# Connections.net
KiCad netlist of a schematic drawn in Altium Designer
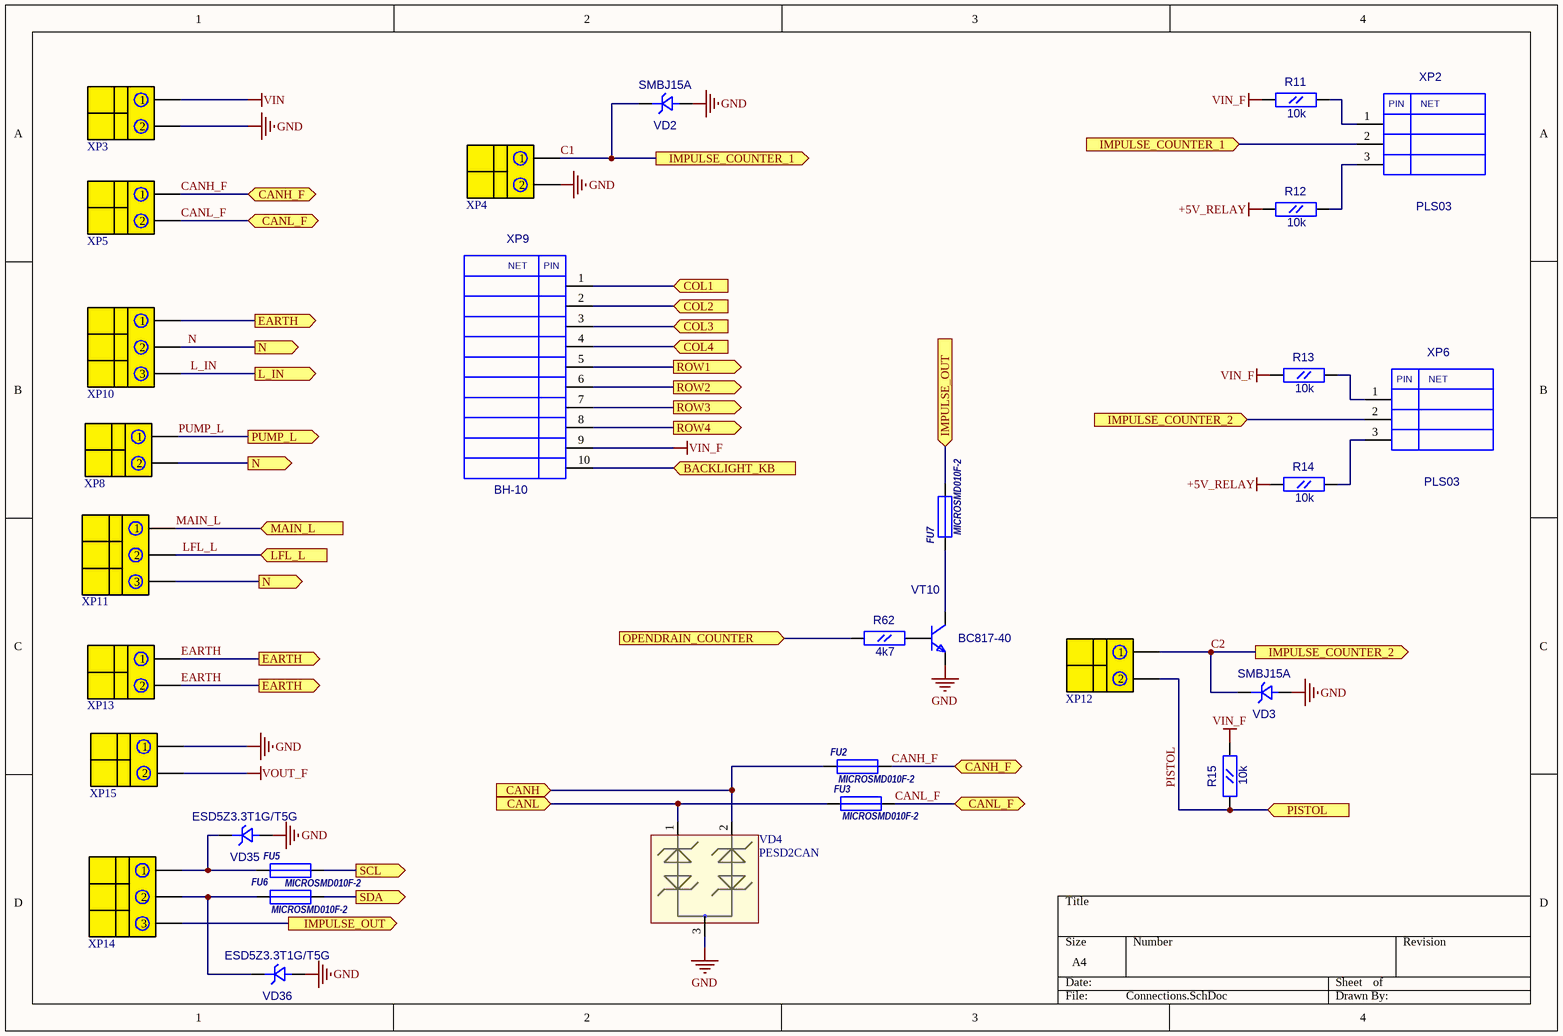
[diagram p0: Connections.SchDoc]

(export (version "E")
  (design (tool "Eeschema 10.0.6"))
  (components
    (comp (ref "FU2")
      (value "MICROSMD010F-2")
      (footprint "RC1210")
      (description "MICROSMD")
      (libsource (lib "gprs_modem_2") (part "MICROSMD"))
    )
    (comp (ref "FU3")
      (value "MICROSMD010F-2")
      (footprint "RC1210")
      (description "MICROSMD")
      (libsource (lib "gprs_modem_2") (part "MICROSMD"))
    )
    (comp (ref "FU5")
      (value "MICROSMD010F-2")
      (footprint "RC1210")
      (description "MICROSMD")
      (libsource (lib "gprs_modem_2") (part "MICROSMD"))
    )
    (comp (ref "FU6")
      (value "MICROSMD010F-2")
      (footprint "RC1210")
      (description "MICROSMD")
      (libsource (lib "gprs_modem_2") (part "MICROSMD"))
    )
    (comp (ref "FU7")
      (value "MICROSMD010F-2")
      (footprint "RC1210")
      (description "MICROSMD")
      (libsource (lib "gprs_modem_2") (part "MICROSMD"))
    )
    (comp (ref "R11")
      (value "10k")
      (footprint "RC0603")
      (description "RC0603")
      (libsource (lib "gprs_modem_2") (part "RC0603"))
    )
    (comp (ref "R12")
      (value "10k")
      (footprint "RC0603")
      (description "RC0603")
      (libsource (lib "gprs_modem_2") (part "RC0603"))
    )
    (comp (ref "R13")
      (value "10k")
      (footprint "RC0603")
      (description "RC0603")
      (libsource (lib "gprs_modem_2") (part "RC0603"))
    )
    (comp (ref "R14")
      (value "10k")
      (footprint "RC0603")
      (description "RC0603")
      (libsource (lib "gprs_modem_2") (part "RC0603"))
    )
    (comp (ref "R15")
      (value "10k")
      (footprint "RC0603")
      (description "RC0603")
      (libsource (lib "gprs_modem_2") (part "RC0603"))
    )
    (comp (ref "R62")
      (value "4k7")
      (footprint "RC0603")
      (description "RC0603")
      (libsource (lib "gprs_modem_2") (part "RC0603"))
    )
    (comp (ref "VD2")
      (value "SMBJ15A")
      (footprint "SMB")
      (description "SMBJ")
      (libsource (lib "gprs_modem_2") (part "SMBJ"))
    )
    (comp (ref "VD3")
      (value "SMBJ15A")
      (footprint "SMB")
      (description "SMBJ")
      (libsource (lib "gprs_modem_2") (part "SMBJ"))
    )
    (comp (ref "VD4")
      (value "PESD2CAN")
      (footprint "SOT-23(123)")
      (description "TVS for CAN")
      (libsource (lib "gprs_modem_2") (part "PESD2CAN"))
    )
    (comp (ref "VD35")
      (value "ESD5Z3.3T1G/T5G")
      (footprint "SOD-523")
      (description "Supressor")
      (libsource (lib "gprs_modem_2") (part "ESD5Z"))
    )
    (comp (ref "VD36")
      (value "ESD5Z3.3T1G/T5G")
      (footprint "SOD-523")
      (description "Supressor")
      (libsource (lib "gprs_modem_2") (part "ESD5Z"))
    )
    (comp (ref "VT10")
      (value "BC817-40")
      (footprint "SOT-23(123)")
      (description "NPN 500ma transistor")
      (libsource (lib "gprs_modem_2") (part "BC846BLT1"))
    )
    (comp (ref "XP2") (value "PLS03") (footprint "PLS-03") (libsource (lib "gprs_modem_2") (part "PLS03")))
    (comp (ref "XP3")
      (value "DG330-2PIN")
      (footprint "DG330-2PIN")
      (libsource (lib "gprs_modem_2") (part "DG330-2PIN"))
    )
    (comp (ref "XP4")
      (value "DG330-2PIN")
      (footprint "DG330-2PIN")
      (libsource (lib "gprs_modem_2") (part "DG330-2PIN"))
    )
    (comp (ref "XP5")
      (value "DG330-2PIN")
      (footprint "DG330-2PIN")
      (libsource (lib "gprs_modem_2") (part "DG330-2PIN"))
    )
    (comp (ref "XP6") (value "PLS03") (footprint "PLS-03") (libsource (lib "gprs_modem_2") (part "PLS03")))
    (comp (ref "XP8")
      (value "DG330-2PIN")
      (footprint "DG330-2PIN")
      (libsource (lib "gprs_modem_2") (part "DG330-2PIN"))
    )
    (comp (ref "XP9") (value "BH-10") (footprint "BH-10") (libsource (lib "gprs_modem_2") (part "BH-10")))
    (comp (ref "XP10")
      (value "DG330-3PIN")
      (footprint "DG330-3PIN")
      (libsource (lib "gprs_modem_2") (part "DG330-3PIN"))
    )
    (comp (ref "XP11")
      (value "DG330-3PIN")
      (footprint "DG330-3PIN")
      (libsource (lib "gprs_modem_2") (part "DG330-3PIN"))
    )
    (comp (ref "XP12")
      (value "DG330-2PIN")
      (footprint "DG330-2PIN")
      (libsource (lib "gprs_modem_2") (part "DG330-2PIN"))
    )
    (comp (ref "XP13")
      (value "DG330-2PIN")
      (footprint "DG330-2PIN")
      (libsource (lib "gprs_modem_2") (part "DG330-2PIN"))
    )
    (comp (ref "XP14")
      (value "DG330-3PIN")
      (footprint "DG330-3PIN")
      (libsource (lib "gprs_modem_2") (part "DG330-3PIN"))
    )
    (comp (ref "XP15")
      (value "DG330-2PIN")
      (footprint "DG330-2PIN")
      (libsource (lib "gprs_modem_2") (part "DG330-2PIN"))
    )
  )
  (nets
    (net (code "1") (name "+5V_RELAY") (class "Default")
      (node (ref "R12") (pin "1") (pinfunction "A_1") (pintype "passive"))
      (node (ref "R14") (pin "1") (pinfunction "A_1") (pintype "passive"))
    )
    (net (code "2") (name "/BACKLIGHT_KB") (class "Default")
      (node (ref "XP9") (pin "10") (pinfunction "10_10") (pintype "passive"))
    )
    (net (code "3") (name "/C1") (class "Default")
      (node (ref "VD2") (pin "2") (pinfunction "K_2") (pintype "passive"))
      (node (ref "XP2") (pin "2") (pinfunction "2_2") (pintype "passive"))
      (node (ref "XP4") (pin "1") (pinfunction "1_1") (pintype "passive"))
    )
    (net (code "4") (name "/C2") (class "Default")
      (node (ref "VD3") (pin "2") (pinfunction "K_2") (pintype "passive"))
      (node (ref "XP12") (pin "1") (pinfunction "1_1") (pintype "passive"))
      (node (ref "XP6") (pin "2") (pinfunction "2_2") (pintype "passive"))
    )
    (net (code "5") (name "/CANH") (class "Default")
      (node (ref "FU2") (pin "1") (pintype "passive"))
      (node (ref "VD4") (pin "2") (pinfunction "2_2") (pintype "passive"))
    )
    (net (code "6") (name "/CANH_F") (class "Default")
      (node (ref "FU2") (pin "2") (pintype "passive"))
      (node (ref "XP5") (pin "1") (pinfunction "1_1") (pintype "passive"))
    )
    (net (code "7") (name "/CANL") (class "Default")
      (node (ref "FU3") (pin "1") (pintype "passive"))
      (node (ref "VD4") (pin "1") (pinfunction "1_1") (pintype "passive"))
    )
    (net (code "8") (name "/CANL_F") (class "Default")
      (node (ref "FU3") (pin "2") (pintype "passive"))
      (node (ref "XP5") (pin "2") (pinfunction "2_2") (pintype "passive"))
    )
    (net (code "9") (name "/COL1") (class "Default")
      (node (ref "XP9") (pin "1") (pinfunction "1_1") (pintype "passive"))
    )
    (net (code "10") (name "/COL2") (class "Default")
      (node (ref "XP9") (pin "2") (pinfunction "2_2") (pintype "passive"))
    )
    (net (code "11") (name "/COL3") (class "Default")
      (node (ref "XP9") (pin "3") (pinfunction "3_3") (pintype "passive"))
    )
    (net (code "12") (name "/COL4") (class "Default")
      (node (ref "XP9") (pin "4") (pinfunction "4_4") (pintype "passive"))
    )
    (net (code "13") (name "/EARTH") (class "Default")
      (node (ref "XP10") (pin "1") (pinfunction "1_1") (pintype "passive"))
      (node (ref "XP13") (pin "1") (pinfunction "1_1") (pintype "passive"))
      (node (ref "XP13") (pin "2") (pinfunction "2_2") (pintype "passive"))
    )
    (net (code "14") (name "/IMPULSE_OUT") (class "Default")
      (node (ref "FU7") (pin "2") (pintype "passive"))
      (node (ref "XP14") (pin "3") (pinfunction "3_3") (pintype "passive"))
    )
    (net (code "15") (name "/LFL_L") (class "Default")
      (node (ref "XP11") (pin "2") (pinfunction "2_2") (pintype "passive"))
    )
    (net (code "16") (name "/L_IN") (class "Default")
      (node (ref "XP10") (pin "3") (pinfunction "3_3") (pintype "passive"))
    )
    (net (code "17") (name "/MAIN_L") (class "Default")
      (node (ref "XP11") (pin "1") (pinfunction "1_1") (pintype "passive"))
    )
    (net (code "18") (name "/N") (class "Default")
      (node (ref "XP10") (pin "2") (pinfunction "2_2") (pintype "passive"))
      (node (ref "XP11") (pin "3") (pinfunction "3_3") (pintype "passive"))
      (node (ref "XP8") (pin "2") (pinfunction "2_2") (pintype "passive"))
    )
    (net (code "19") (name "/OPENDRAIN_COUNTER") (class "Default")
      (node (ref "R62") (pin "1") (pinfunction "A_1") (pintype "passive"))
    )
    (net (code "20") (name "/PISTOL") (class "Default")
      (node (ref "R15") (pin "1") (pinfunction "A_1") (pintype "passive"))
      (node (ref "XP12") (pin "2") (pinfunction "2_2") (pintype "passive"))
    )
    (net (code "21") (name "/PUMP_L") (class "Default")
      (node (ref "XP8") (pin "1") (pinfunction "1_1") (pintype "passive"))
    )
    (net (code "22") (name "/ROW1") (class "Default")
      (node (ref "XP9") (pin "5") (pinfunction "5_5") (pintype "passive"))
    )
    (net (code "23") (name "/ROW2") (class "Default")
      (node (ref "XP9") (pin "6") (pinfunction "6_6") (pintype "passive"))
    )
    (net (code "24") (name "/ROW3") (class "Default")
      (node (ref "XP9") (pin "7") (pinfunction "7_7") (pintype "passive"))
    )
    (net (code "25") (name "/ROW4") (class "Default")
      (node (ref "XP9") (pin "8") (pinfunction "8_8") (pintype "passive"))
    )
    (net (code "26") (name "/SCL") (class "Default") (node (ref "FU5") (pin "2") (pintype "passive")))
    (net (code "27") (name "/SDA") (class "Default") (node (ref "FU6") (pin "2") (pintype "passive")))
    (net (code "28") (name "GND") (class "Default")
      (node (ref "VD2") (pin "1") (pinfunction "A_1") (pintype "passive"))
      (node (ref "VD3") (pin "1") (pinfunction "A_1") (pintype "passive"))
      (node (ref "VD35") (pin "1") (pinfunction "A_1") (pintype "passive"))
      (node (ref "VD36") (pin "1") (pinfunction "A_1") (pintype "passive"))
      (node (ref "VD4") (pin "3") (pinfunction "3_3") (pintype "passive"))
      (node (ref "VT10") (pin "2") (pinfunction "E_2") (pintype "passive"))
      (node (ref "XP15") (pin "1") (pinfunction "1_1") (pintype "passive"))
      (node (ref "XP3") (pin "2") (pinfunction "2_2") (pintype "passive"))
      (node (ref "XP4") (pin "2") (pinfunction "2_2") (pintype "passive"))
    )
    (net (code "29") (name "Net-(R11-B)") (class "Default")
      (node (ref "R11") (pin "2") (pinfunction "B_2") (pintype "passive"))
      (node (ref "XP2") (pin "1") (pinfunction "1_1") (pintype "passive"))
    )
    (net (code "30") (name "Net-(R12-B)") (class "Default")
      (node (ref "R12") (pin "2") (pinfunction "B_2") (pintype "passive"))
      (node (ref "XP2") (pin "3") (pinfunction "3_3") (pintype "passive"))
    )
    (net (code "31") (name "Net-(R13-B)") (class "Default")
      (node (ref "R13") (pin "2") (pinfunction "B_2") (pintype "passive"))
      (node (ref "XP6") (pin "1") (pinfunction "1_1") (pintype "passive"))
    )
    (net (code "32") (name "Net-(R14-B)") (class "Default")
      (node (ref "R14") (pin "2") (pinfunction "B_2") (pintype "passive"))
      (node (ref "XP6") (pin "3") (pinfunction "3_3") (pintype "passive"))
    )
    (net (code "33") (name "Net-(R62-B)") (class "Default")
      (node (ref "R62") (pin "2") (pinfunction "B_2") (pintype "passive"))
      (node (ref "VT10") (pin "1") (pinfunction "B_1") (pintype "passive"))
    )
    (net (code "34") (name "Net-(VD35-K)") (class "Default")
      (node (ref "FU5") (pin "1") (pintype "passive"))
      (node (ref "VD35") (pin "2") (pinfunction "K_2") (pintype "passive"))
      (node (ref "XP14") (pin "1") (pinfunction "1_1") (pintype "passive"))
    )
    (net (code "35") (name "Net-(VD36-K)") (class "Default")
      (node (ref "FU6") (pin "1") (pintype "passive"))
      (node (ref "VD36") (pin "2") (pinfunction "K_2") (pintype "passive"))
      (node (ref "XP14") (pin "2") (pinfunction "2_2") (pintype "passive"))
    )
    (net (code "36") (name "Net-(VT10-C)") (class "Default")
      (node (ref "FU7") (pin "1") (pintype "passive"))
      (node (ref "VT10") (pin "3") (pinfunction "C_3") (pintype "passive"))
    )
    (net (code "37") (name "VIN") (class "Default")
      (node (ref "XP3") (pin "1") (pinfunction "1_1") (pintype "passive"))
    )
    (net (code "38") (name "VIN_F") (class "Default")
      (node (ref "R11") (pin "1") (pinfunction "A_1") (pintype "passive"))
      (node (ref "R13") (pin "1") (pinfunction "A_1") (pintype "passive"))
      (node (ref "R15") (pin "2") (pinfunction "B_2") (pintype "passive"))
      (node (ref "XP9") (pin "9") (pinfunction "9_9") (pintype "passive"))
    )
    (net (code "39") (name "VOUT_F") (class "Default")
      (node (ref "XP15") (pin "2") (pinfunction "2_2") (pintype "passive"))
    )
  )
)
